# SPI.net
KiCad netlist of a schematic drawn in Altium Designer
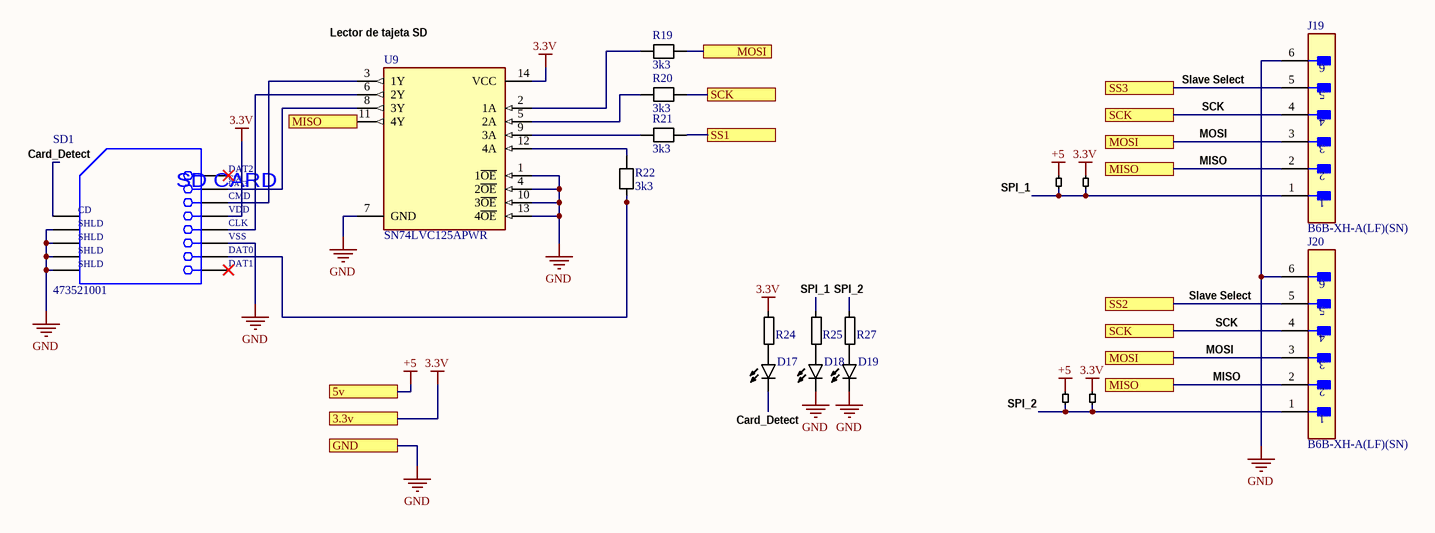
[diagram p0: SPI.SchDoc]

(export (version "E")
  (design (tool "Eeschema 10.0.6"))
  (components
    (comp (ref "D17")
      (value "597-3305-607F")
      (footprint "0805 LED")
      (description "LED Uni-Color Green 4-Pin Chip 0805 T/R")
      (libsource (lib "597-3305-607F") (part "597-3305-607F"))
    )
    (comp (ref "D18")
      (value "597-3305-607F")
      (footprint "0805 LED")
      (description "LED Uni-Color Green 4-Pin Chip 0805 T/R")
      (libsource (lib "597-3305-607F") (part "597-3305-607F"))
    )
    (comp (ref "D19")
      (value "597-3305-607F")
      (footprint "0805 LED")
      (description "LED Uni-Color Green 4-Pin Chip 0805 T/R")
      (libsource (lib "597-3305-607F") (part "597-3305-607F"))
    )
    (comp (ref "J19")
      (value "B6B-XH-A(LF)(SN)")
      (footprint "FP-B6B-XH-A_LF_SN-MFG")
      (description "CONN HEADER VERT 6POS 2.5MM")
      (libsource (lib "Altium Content Vault") (part "f2cb566baf1c37ab5a3b8e90bbeafd6"))
    )
    (comp (ref "J20")
      (value "B6B-XH-A(LF)(SN)")
      (footprint "FP-B6B-XH-A_LF_SN-MFG")
      (description "CONN HEADER VERT 6POS 2.5MM")
      (libsource (lib "Altium Content Vault") (part "f2cb566baf1c37ab5a3b8e90bbeafd6"))
    )
    (comp (ref "R19")
      (value "3k3")
      (footprint "1206")
      (fields (field (name "MP") "RGC1206DTC10K0"))
      (libsource (lib "RGC1206DTC10K0") (part "RGC1206DTC10K0"))
    )
    (comp (ref "R20")
      (value "3k3")
      (footprint "1206")
      (fields (field (name "MP") "RGC1206DTC10K0"))
      (libsource (lib "RGC1206DTC10K0") (part "RGC1206DTC10K0"))
    )
    (comp (ref "R21")
      (value "3k3")
      (footprint "1206")
      (fields (field (name "MP") "RGC1206DTC10K0"))
      (libsource (lib "RGC1206DTC10K0") (part "RGC1206DTC10K0"))
    )
    (comp (ref "R22")
      (value "3k3")
      (footprint "1206")
      (fields (field (name "MP") "RGC1206DTC10K0"))
      (libsource (lib "RGC1206DTC10K0") (part "RGC1206DTC10K0"))
    )
    (comp (ref "R24")
      (value "CR0805-JW-221ELF")
      (footprint "0805 res")
      (description "220 Ohms Â±5% 0.125W, 1/8W Chip Resistor 0805 (2012 Metric) Moisture Resistant Thick Film")
      (fields (field (name "MF") "Bourns"))
      (libsource (lib "CR0805-JW-221ELF") (part "CR0805-JW-221ELF"))
    )
    (comp (ref "R25")
      (value "CR0805-JW-221ELF")
      (footprint "0805 res")
      (description "220 Ohms Â±5% 0.125W, 1/8W Chip Resistor 0805 (2012 Metric) Moisture Resistant Thick Film")
      (fields (field (name "MF") "Bourns"))
      (libsource (lib "CR0805-JW-221ELF") (part "CR0805-JW-221ELF"))
    )
    (comp (ref "R27")
      (value "CR0805-JW-221ELF")
      (footprint "0805 res")
      (description "220 Ohms Â±5% 0.125W, 1/8W Chip Resistor 0805 (2012 Metric) Moisture Resistant Thick Film")
      (fields (field (name "MF") "Bourns"))
      (libsource (lib "CR0805-JW-221ELF") (part "CR0805-JW-221ELF"))
    )
    (comp (ref "SD1")
      (value "473521001")
      (footprint "MOLX-473521001_V")
      (description "MicroSD(TM), Pitch 1.1 mm, 8 Position, Height 1.88 mm, -20 to 85 degC, RoHS, Tape and Reel")
      (fields (field (name "MANUFACTURER") "Molex"))
      (libsource (lib "Altium Content Vault") (part "CN-SD-8-1SW-4S"))
    )
    (comp (ref "U9")
      (value "SN74LVC125APWR")
      (footprint "FP-PW0014A-IPC_B")
      (description "IC BUF NON-INVERT 3.6V 14TSSOP")
      (libsource (lib "Altium Content Vault") (part "0c185306b27c65c3e4a0d950f37c68a"))
    )
    (comp (ref "W2") (value "Jumper") (footprint "Jumper Mid") (libsource (lib "Schlib1") (part "Jumper")))
    (comp (ref "W9") (value "Jumper") (footprint "Jumper Mid") (libsource (lib "Schlib1") (part "Jumper")))
    (comp (ref "W10") (value "Jumper") (footprint "Jumper Mid") (libsource (lib "Schlib1") (part "Jumper")))
    (comp (ref "W11") (value "Jumper") (footprint "Jumper Mid") (libsource (lib "Schlib1") (part "Jumper")))
  )
  (nets
    (net (code "1") (name "+5") (class "Default")
      (node (ref "W2") (pin "2") (pinfunction "2_2") (pintype "passive"))
      (node (ref "W9") (pin "2") (pinfunction "2_2") (pintype "passive"))
    )
    (net (code "2") (name "/Card_Detect") (class "Default")
      (node (ref "D17") (pin "C") (pinfunction "C_C") (pintype "passive"))
      (node (ref "SD1") (pin "9") (pinfunction "CD_9") (pintype "passive"))
    )
    (net (code "3") (name "/MISO") (class "Default")
      (node (ref "J19") (pin "2") (pinfunction "2_2") (pintype "passive"))
      (node (ref "J20") (pin "2") (pinfunction "2_2") (pintype "passive"))
      (node (ref "U9") (pin "11") (pinfunction "4Y_11") (pintype "output"))
    )
    (net (code "4") (name "/MOSI") (class "Default")
      (node (ref "J19") (pin "3") (pinfunction "3_3") (pintype "passive"))
      (node (ref "J20") (pin "3") (pinfunction "3_3") (pintype "passive"))
      (node (ref "R19") (pin "2") (pinfunction "2_2") (pintype "passive"))
    )
    (net (code "5") (name "/SCK") (class "Default")
      (node (ref "J19") (pin "4") (pinfunction "4_4") (pintype "passive"))
      (node (ref "J20") (pin "4") (pinfunction "4_4") (pintype "passive"))
      (node (ref "R20") (pin "2") (pinfunction "2_2") (pintype "passive"))
    )
    (net (code "6") (name "/SPI_1") (class "Default")
      (node (ref "J19") (pin "1") (pinfunction "1_1") (pintype "passive"))
      (node (ref "R25") (pin "1") (pinfunction "1_1") (pintype "passive"))
      (node (ref "W10") (pin "1") (pinfunction "1_1") (pintype "passive"))
      (node (ref "W2") (pin "1") (pinfunction "1_1") (pintype "passive"))
    )
    (net (code "7") (name "/SPI_2") (class "Default")
      (node (ref "J20") (pin "1") (pinfunction "1_1") (pintype "passive"))
      (node (ref "R27") (pin "1") (pinfunction "1_1") (pintype "passive"))
      (node (ref "W11") (pin "1") (pinfunction "1_1") (pintype "passive"))
      (node (ref "W9") (pin "1") (pinfunction "1_1") (pintype "passive"))
    )
    (net (code "8") (name "/SS1") (class "Default")
      (node (ref "R21") (pin "2") (pinfunction "2_2") (pintype "passive"))
    )
    (net (code "9") (name "/SS2") (class "Default")
      (node (ref "J20") (pin "5") (pinfunction "5_5") (pintype "passive"))
    )
    (net (code "10") (name "/SS3") (class "Default")
      (node (ref "J19") (pin "5") (pinfunction "5_5") (pintype "passive"))
    )
    (net (code "11") (name "3.3V") (class "Default")
      (node (ref "R24") (pin "1") (pinfunction "1_1") (pintype "passive"))
      (node (ref "SD1") (pin "4") (pinfunction "VDD_4") (pintype "passive"))
      (node (ref "U9") (pin "14") (pinfunction "VCC_14") (pintype "power_in"))
      (node (ref "W10") (pin "2") (pinfunction "2_2") (pintype "passive"))
      (node (ref "W11") (pin "2") (pinfunction "2_2") (pintype "passive"))
    )
    (net (code "12") (name "GND") (class "Default")
      (node (ref "D18") (pin "C") (pinfunction "C_C") (pintype "passive"))
      (node (ref "D19") (pin "C") (pinfunction "C_C") (pintype "passive"))
      (node (ref "J19") (pin "6") (pinfunction "6_6") (pintype "passive"))
      (node (ref "J20") (pin "6") (pinfunction "6_6") (pintype "passive"))
      (node (ref "SD1") (pin "10") (pinfunction "SHLD_10") (pintype "passive"))
      (node (ref "SD1") (pin "11") (pinfunction "SHLD_11") (pintype "passive"))
      (node (ref "SD1") (pin "12") (pinfunction "SHLD_12") (pintype "passive"))
      (node (ref "SD1") (pin "13") (pinfunction "SHLD_13") (pintype "passive"))
      (node (ref "SD1") (pin "6") (pinfunction "VSS_6") (pintype "passive"))
      (node (ref "U9") (pin "1") (pinfunction "1~{OE}_1") (pintype "input"))
      (node (ref "U9") (pin "10") (pinfunction "3~{OE}_10") (pintype "input"))
      (node (ref "U9") (pin "13") (pinfunction "4~{OE}_13") (pintype "input"))
      (node (ref "U9") (pin "4") (pinfunction "2~{OE}_4") (pintype "input"))
      (node (ref "U9") (pin "7") (pinfunction "GND_7") (pintype "power_in"))
    )
    (net (code "13") (name "Net-(D17-PadA)") (class "Default")
      (node (ref "D17") (pin "A") (pinfunction "A_A") (pintype "passive"))
      (node (ref "R24") (pin "2") (pinfunction "2_2") (pintype "passive"))
    )
    (net (code "14") (name "Net-(D18-PadA)") (class "Default")
      (node (ref "D18") (pin "A") (pinfunction "A_A") (pintype "passive"))
      (node (ref "R25") (pin "2") (pinfunction "2_2") (pintype "passive"))
    )
    (net (code "15") (name "Net-(D19-PadA)") (class "Default")
      (node (ref "D19") (pin "A") (pinfunction "A_A") (pintype "passive"))
      (node (ref "R27") (pin "2") (pinfunction "2_2") (pintype "passive"))
    )
    (net (code "16") (name "Net-(SD1-CD{slash}DAT3)") (class "Default")
      (node (ref "SD1") (pin "2") (pinfunction "CD/DAT3_2") (pintype "passive"))
      (node (ref "U9") (pin "8") (pinfunction "3Y_8") (pintype "output"))
    )
    (net (code "17") (name "Net-(SD1-CLK)") (class "Default")
      (node (ref "SD1") (pin "5") (pinfunction "CLK_5") (pintype "passive"))
      (node (ref "U9") (pin "6") (pinfunction "2Y_6") (pintype "output"))
    )
    (net (code "18") (name "Net-(SD1-CMD)") (class "Default")
      (node (ref "SD1") (pin "3") (pinfunction "CMD_3") (pintype "passive"))
      (node (ref "U9") (pin "3") (pinfunction "1Y_3") (pintype "output"))
    )
    (net (code "19") (name "Net-(SD1-DAT0)") (class "Default")
      (node (ref "R22") (pin "2") (pinfunction "2_2") (pintype "passive"))
      (node (ref "SD1") (pin "7") (pinfunction "DAT0_7") (pintype "passive"))
    )
    (net (code "20") (name "Net-(U9-1A)") (class "Default")
      (node (ref "R19") (pin "1") (pinfunction "1_1") (pintype "passive"))
      (node (ref "U9") (pin "2") (pinfunction "1A_2") (pintype "input"))
    )
    (net (code "21") (name "Net-(U9-2A)") (class "Default")
      (node (ref "R20") (pin "1") (pinfunction "1_1") (pintype "passive"))
      (node (ref "U9") (pin "5") (pinfunction "2A_5") (pintype "input"))
    )
    (net (code "22") (name "Net-(U9-3A)") (class "Default")
      (node (ref "R21") (pin "1") (pinfunction "1_1") (pintype "passive"))
      (node (ref "U9") (pin "9") (pinfunction "3A_9") (pintype "input"))
    )
    (net (code "23") (name "Net-(U9-4A)") (class "Default")
      (node (ref "R22") (pin "1") (pinfunction "1_1") (pintype "passive"))
      (node (ref "U9") (pin "12") (pinfunction "4A_12") (pintype "input"))
    )
    (net (code "24") (name "unconnected-(SD1-DAT1-Pad8)") (class "Default")
      (node (ref "SD1") (pin "8") (pinfunction "DAT1_8") (pintype "passive+no_connect"))
    )
    (net (code "25") (name "unconnected-(SD1-DAT2-Pad1)") (class "Default")
      (node (ref "SD1") (pin "1") (pinfunction "DAT2_1") (pintype "passive+no_connect"))
    )
  )
)
